# sensor_board.net
KiCad netlist of a schematic drawn in EAGLE
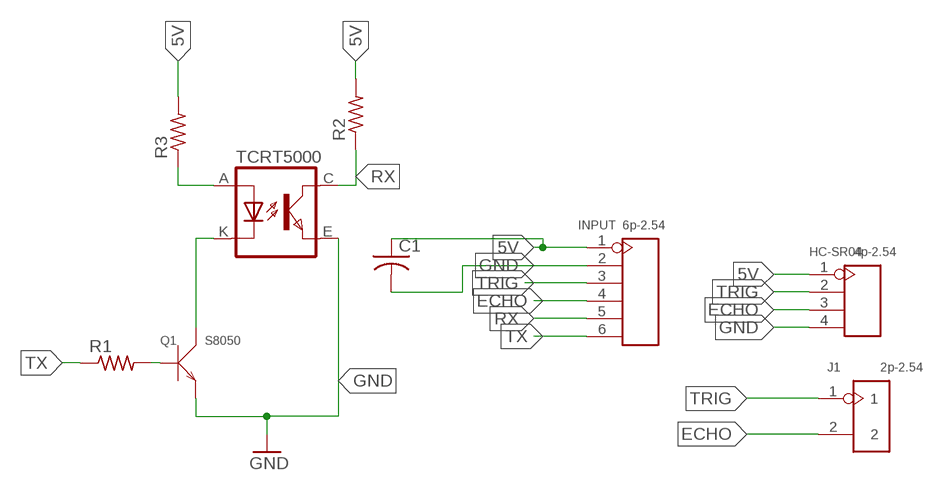
[diagram p0: schematic, sheet 1]

(export (version "E")
  (design (tool "Eeschema 10.0.6"))
  (components
    (comp (ref "C1")
      (value "C-USC1206")
      (footprint "eagle-import:C1206")
      (libsource (lib "eagle-import") (part "C-USC1206"))
    )
    (comp (ref "HC-SR04")
      (value "4p-2.54")
      (footprint "eagle-import:H4-2.54")
      (fields (field (name "MPN") "F185-1104A1BSYA1"))
      (libsource (lib "eagle-import") (part "DIP-BLACK-FEMALE-HEADER-VERT(4P-2.54)"))
    )
    (comp (ref "INPUT")
      (value "6p-2.54")
      (footprint "eagle-import:H6-2.54")
      (fields (field (name "MPN") "F185-1106A1BSYC1"))
      (libsource (lib "eagle-import") (part "DIP-BLACK-FEMALE-HEADER-VERT(6P-2.54)"))
    )
    (comp (ref "J1")
      (value "2p-2.54")
      (footprint "eagle-import:H2-2.54")
      (fields (field (name "MPN") "P125-1102A0BS116A1"))
      (libsource (lib "eagle-import") (part "DIP-BLACK-MALE-HEADER-VERT(2P-2.54)"))
    )
    (comp (ref "Q1")
      (value "S8050")
      (footprint "eagle-import:SOT-23")
      (libsource (lib "eagle-import") (part "SMD-TRANSISTORS-NPN-25V-500MW-S8050(SOT-23)"))
    )
    (comp (ref "R1")
      (value "R-US_R1206")
      (footprint "eagle-import:R1206")
      (libsource (lib "eagle-import") (part "R-US_R1206"))
    )
    (comp (ref "R2")
      (value "R-US_R1206")
      (footprint "eagle-import:R1206")
      (libsource (lib "eagle-import") (part "R-US_R1206"))
    )
    (comp (ref "R3")
      (value "R-US_R1206")
      (footprint "eagle-import:R1206")
      (libsource (lib "eagle-import") (part "R-US_R1206"))
    )
    (comp (ref "TCRT5000")
      (value "TCRT5000")
      (footprint "eagle-import:TCRT5000")
      (libsource (lib "eagle-import") (part "TCRT5000"))
    )
  )
  (nets
    (net (code "1") (name "5V") (class "Default")
      (node (ref "C1") (pin "1") (pinfunction "1_1") (pintype "passive"))
      (node (ref "HC-SR04") (pin "1") (pinfunction "P$1_1") (pintype "bidirectional"))
      (node (ref "INPUT") (pin "1") (pinfunction "1_1") (pintype "bidirectional"))
      (node (ref "R2") (pin "2") (pinfunction "2_2") (pintype "passive"))
      (node (ref "R3") (pin "2") (pinfunction "2_2") (pintype "passive"))
    )
    (net (code "2") (name "ECHO") (class "Default")
      (node (ref "HC-SR04") (pin "3") (pinfunction "P$3_3") (pintype "bidirectional"))
      (node (ref "INPUT") (pin "4") (pinfunction "4_4") (pintype "bidirectional"))
      (node (ref "J1") (pin "2") (pinfunction "2_2") (pintype "bidirectional"))
    )
    (net (code "3") (name "GND") (class "Default")
      (node (ref "C1") (pin "2") (pinfunction "2_2") (pintype "passive"))
      (node (ref "HC-SR04") (pin "4") (pinfunction "P$4_4") (pintype "bidirectional"))
      (node (ref "INPUT") (pin "2") (pinfunction "2_2") (pintype "bidirectional"))
      (node (ref "Q1") (pin "2") (pinfunction "E_2") (pintype "passive"))
      (node (ref "TCRT5000") (pin "E") (pinfunction "EMITTER_E") (pintype "passive"))
    )
    (net (code "4") (name "Net-(Q1-B)") (class "Default")
      (node (ref "Q1") (pin "1") (pinfunction "B_1") (pintype "passive"))
      (node (ref "R1") (pin "2") (pinfunction "2_2") (pintype "passive"))
    )
    (net (code "5") (name "Net-(Q1-C)") (class "Default")
      (node (ref "Q1") (pin "3") (pinfunction "C_3") (pintype "passive"))
      (node (ref "TCRT5000") (pin "K") (pinfunction "CATHODE_K") (pintype "passive"))
    )
    (net (code "6") (name "Net-(TCRT5000-ANODE)") (class "Default")
      (node (ref "R3") (pin "1") (pinfunction "1_1") (pintype "passive"))
      (node (ref "TCRT5000") (pin "A") (pinfunction "ANODE_A") (pintype "passive"))
    )
    (net (code "7") (name "RX") (class "Default")
      (node (ref "INPUT") (pin "5") (pinfunction "5_5") (pintype "bidirectional"))
      (node (ref "R2") (pin "1") (pinfunction "1_1") (pintype "passive"))
      (node (ref "TCRT5000") (pin "C") (pinfunction "COLLECTOR_C") (pintype "passive"))
    )
    (net (code "8") (name "TRIG") (class "Default")
      (node (ref "HC-SR04") (pin "2") (pinfunction "P$2_2") (pintype "bidirectional"))
      (node (ref "INPUT") (pin "3") (pinfunction "3_3") (pintype "bidirectional"))
      (node (ref "J1") (pin "1") (pinfunction "1_1") (pintype "bidirectional"))
    )
    (net (code "9") (name "TX") (class "Default")
      (node (ref "INPUT") (pin "6") (pinfunction "6_6") (pintype "bidirectional"))
      (node (ref "R1") (pin "1") (pinfunction "1_1") (pintype "passive"))
    )
  )
)
